# PLC-_-V1.net
KiCad netlist of a schematic drawn in Altium Designer
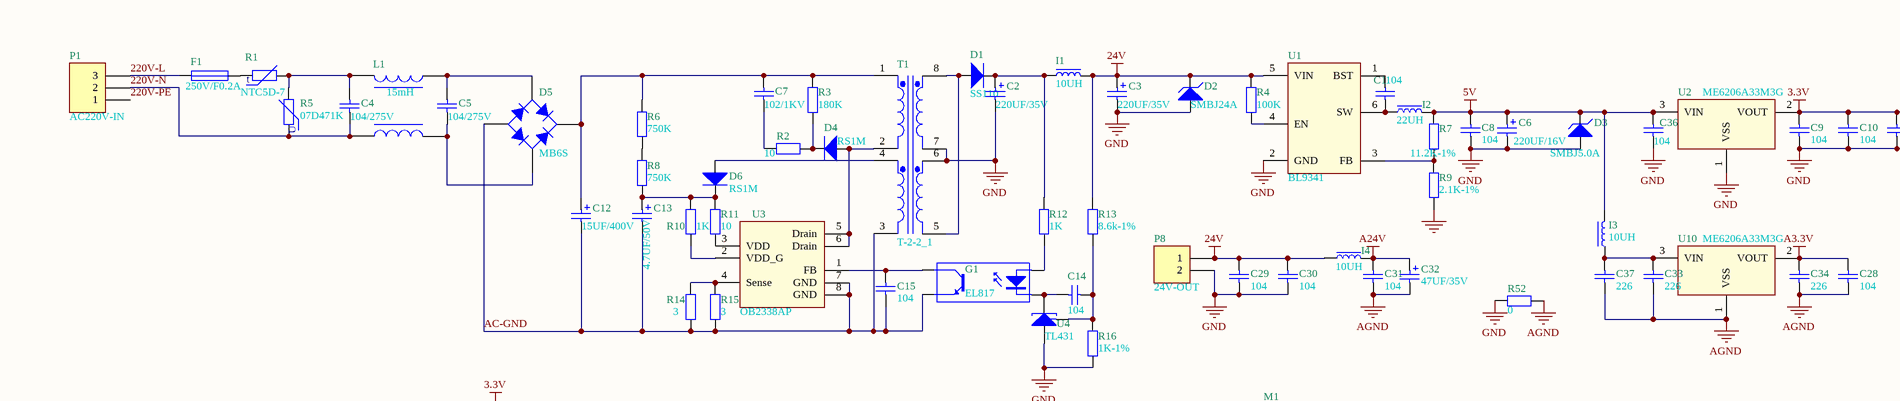
[diagram p0: PLC-无线通讯版-V1.SchDoc, top left]
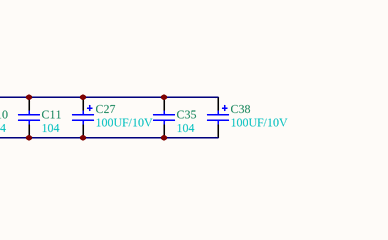
[diagram p1: PLC-无线通讯版-V1.SchDoc, top right]
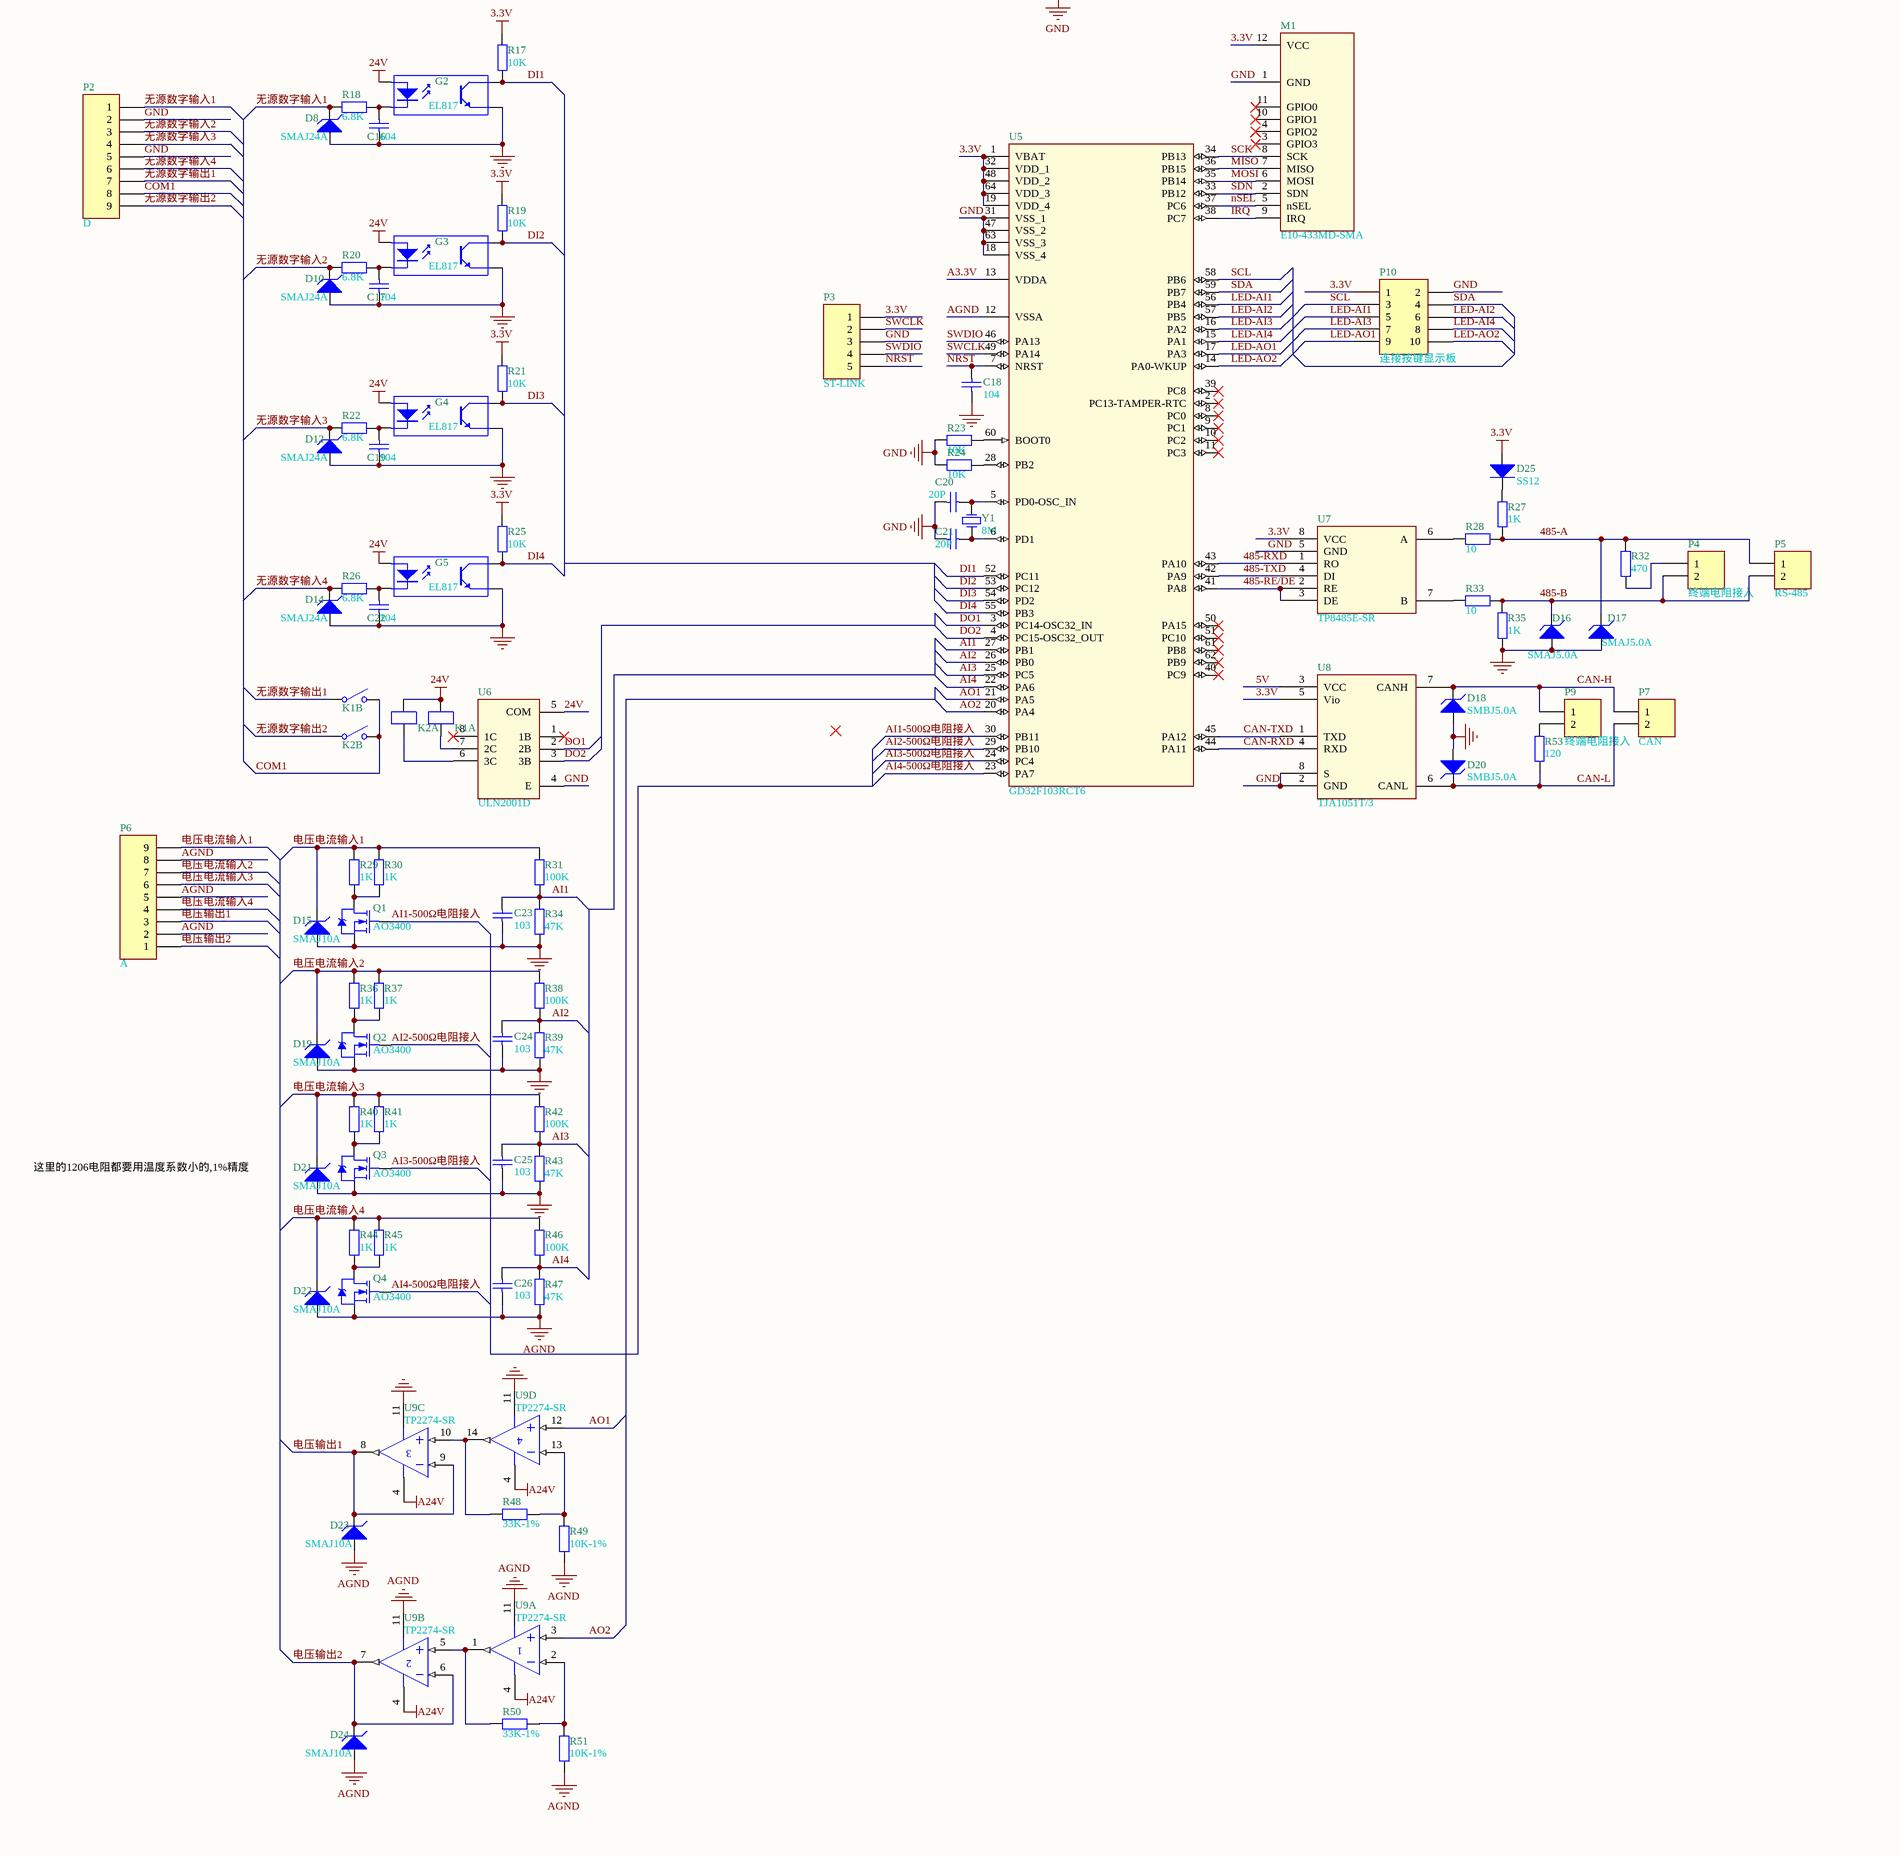
[diagram p2: PLC-无线通讯版-V1.SchDoc, bottom left]
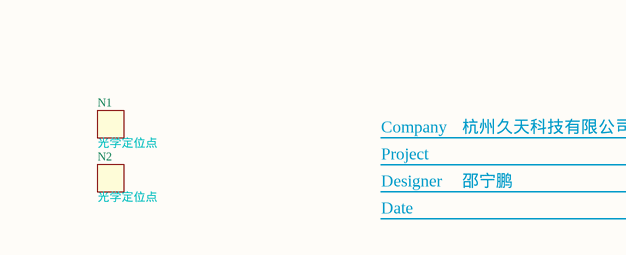
[diagram p3: PLC-无线通讯版-V1.SchDoc, bottom right]

(export (version "E")
  (design (tool "Eeschema 10.0.6"))
  (components
    (comp (ref "C1")
      (value "104")
      (footprint "C-0603")
      (description "Capacitor")
      (fields (field (name "PUBLISHER") "Altium Limited"))
      (libsource (lib "元件2.0") (part "Cap"))
    )
    (comp (ref "C2")
      (value "220UF/35V")
      (footprint "贴片固态电容8*10-M")
      (description "电解电容")
      (fields (field (name "PUBLISHER") "Altium Limited"))
      (libsource (lib "2电容-V1.0") (part "Cap Pol1"))
    )
    (comp (ref "C3")
      (value "220UF/35V")
      (footprint "贴片固态电容8*10-M")
      (description "电解电容")
      (fields (field (name "PUBLISHER") "Altium Limited"))
      (libsource (lib "2电容-V1.0") (part "Cap Pol1"))
    )
    (comp (ref "C4")
      (value "104/275V")
      (footprint "安规电容 脚距10")
      (description "Capacitor")
      (fields (field (name "PUBLISHER") "Altium Limited"))
      (libsource (lib "元件2.0") (part "Cap"))
    )
    (comp (ref "C5")
      (value "104/275V")
      (footprint "安规电容 脚距10")
      (description "Capacitor")
      (fields (field (name "PUBLISHER") "Altium Limited"))
      (libsource (lib "元件2.0") (part "Cap"))
    )
    (comp (ref "C6")
      (value "220UF/16V")
      (footprint "贴片固态电容6.3*7.7")
      (description "Polarized Capacitor (Radial)")
      (fields (field (name "PUBLISHER") "Altium Limited"))
      (libsource (lib "元件2.0") (part "Cap Pol1"))
    )
    (comp (ref "C7")
      (value "102/1KV")
      (footprint "C-1206-M")
      (description "0805")
      (fields (field (name "PUBLISHER") "Altium Limited"))
      (libsource (lib "2电容-V1.0") (part "Cap-0603"))
    )
    (comp (ref "C8")
      (value "104")
      (footprint "C-0603")
      (description "Capacitor")
      (fields (field (name "PUBLISHER") "Altium Limited"))
      (libsource (lib "元件2.0") (part "Cap"))
    )
    (comp (ref "C9")
      (value "104")
      (footprint "C-0603")
      (description "Capacitor")
      (fields (field (name "PUBLISHER") "Altium Limited"))
      (libsource (lib "元件2.0") (part "Cap"))
    )
    (comp (ref "C10")
      (value "104")
      (footprint "C-0603")
      (description "Capacitor")
      (fields (field (name "PUBLISHER") "Altium Limited"))
      (libsource (lib "元件2.0") (part "Cap"))
    )
    (comp (ref "C11")
      (value "104")
      (footprint "C-0603")
      (description "Capacitor")
      (fields (field (name "PUBLISHER") "Altium Limited"))
      (libsource (lib "元件2.0") (part "Cap"))
    )
    (comp (ref "C12")
      (value "15UF/400V")
      (footprint "电解电容10*20蓝色")
      (description "电解电容")
      (fields (field (name "PUBLISHER") "Altium Limited"))
      (libsource (lib "2电容-V1.0") (part "Cap Pol1"))
    )
    (comp (ref "C13")
      (value "4.7UF/50V")
      (footprint "贴片固态电容4*5.3")
      (description "电解电容")
      (fields (field (name "PUBLISHER") "Altium Limited"))
      (libsource (lib "2电容-V1.0") (part "Cap Pol1"))
    )
    (comp (ref "C14")
      (value "104")
      (footprint "C-0603")
      (description "Capacitor")
      (fields (field (name "PUBLISHER") "Altium Limited"))
      (libsource (lib "元件2.0") (part "Cap"))
    )
    (comp (ref "C15")
      (value "104")
      (footprint "C-0603")
      (description "Capacitor")
      (fields (field (name "PUBLISHER") "Altium Limited"))
      (libsource (lib "元件2.0") (part "Cap"))
    )
    (comp (ref "C16")
      (value "104")
      (footprint "C-0603")
      (description "0805")
      (fields (field (name "PUBLISHER") "Altium Limited"))
      (libsource (lib "2电容-V1.0") (part "Cap-0603"))
    )
    (comp (ref "C17")
      (value "104")
      (footprint "C-0603")
      (description "0805")
      (fields (field (name "PUBLISHER") "Altium Limited"))
      (libsource (lib "2电容-V1.0") (part "Cap-0603"))
    )
    (comp (ref "C18")
      (value "104")
      (footprint "C-0603")
      (description "0805")
      (fields (field (name "PUBLISHER") "Altium Limited"))
      (libsource (lib "2电容-V1.0") (part "Cap-0603"))
    )
    (comp (ref "C19")
      (value "104")
      (footprint "C-0603")
      (description "0805")
      (fields (field (name "PUBLISHER") "Altium Limited"))
      (libsource (lib "2电容-V1.0") (part "Cap-0603"))
    )
    (comp (ref "C20")
      (value "20P")
      (footprint "C-0603")
      (description "0805")
      (fields (field (name "PUBLISHER") "Altium Limited"))
      (libsource (lib "2电容-V1.0") (part "Cap-0603"))
    )
    (comp (ref "C21")
      (value "20P")
      (footprint "C-0603")
      (description "0805")
      (fields (field (name "PUBLISHER") "Altium Limited"))
      (libsource (lib "2电容-V1.0") (part "Cap-0603"))
    )
    (comp (ref "C22")
      (value "104")
      (footprint "C-0603")
      (description "0805")
      (fields (field (name "PUBLISHER") "Altium Limited"))
      (libsource (lib "2电容-V1.0") (part "Cap-0603"))
    )
    (comp (ref "C23")
      (value "103")
      (footprint "C-0603")
      (description "0805")
      (fields (field (name "PUBLISHER") "Altium Limited"))
      (libsource (lib "2电容-V1.0") (part "Cap-0603"))
    )
    (comp (ref "C24")
      (value "103")
      (footprint "C-0603")
      (description "0805")
      (fields (field (name "PUBLISHER") "Altium Limited"))
      (libsource (lib "2电容-V1.0") (part "Cap-0603"))
    )
    (comp (ref "C25")
      (value "103")
      (footprint "C-0603")
      (description "0805")
      (fields (field (name "PUBLISHER") "Altium Limited"))
      (libsource (lib "2电容-V1.0") (part "Cap-0603"))
    )
    (comp (ref "C26")
      (value "103")
      (footprint "C-0603")
      (description "0805")
      (fields (field (name "PUBLISHER") "Altium Limited"))
      (libsource (lib "2电容-V1.0") (part "Cap-0603"))
    )
    (comp (ref "C27")
      (value "100UF/10V")
      (footprint "贴片固态电容5*5.3")
      (description "Polarized Capacitor (Radial)")
      (fields (field (name "PUBLISHER") "Altium Limited"))
      (libsource (lib "元件2.0") (part "Cap Pol1"))
    )
    (comp (ref "C28")
      (value "104")
      (footprint "C-0603")
      (description "Capacitor")
      (fields (field (name "PUBLISHER") "Altium Limited"))
      (libsource (lib "元件2.0") (part "Cap"))
    )
    (comp (ref "C29")
      (value "104")
      (footprint "C-0603")
      (description "Capacitor")
      (fields (field (name "PUBLISHER") "Altium Limited"))
      (libsource (lib "元件2.0") (part "Cap"))
    )
    (comp (ref "C30")
      (value "104")
      (footprint "C-0603")
      (description "Capacitor")
      (fields (field (name "PUBLISHER") "Altium Limited"))
      (libsource (lib "元件2.0") (part "Cap"))
    )
    (comp (ref "C31")
      (value "104")
      (footprint "C-0603")
      (description "Capacitor")
      (fields (field (name "PUBLISHER") "Altium Limited"))
      (libsource (lib "元件2.0") (part "Cap"))
    )
    (comp (ref "C32")
      (value "47UF/35V")
      (footprint "贴片固态电容6.3*5.3-M")
      (description "Polarized Capacitor (Radial)")
      (fields (field (name "PUBLISHER") "Altium Limited"))
      (libsource (lib "元件2.0") (part "Cap Pol1"))
    )
    (comp (ref "C33")
      (value "226")
      (footprint "C-0805")
      (description "Capacitor")
      (fields (field (name "PUBLISHER") "Altium Limited"))
      (libsource (lib "元件2.0") (part "Cap"))
    )
    (comp (ref "C34")
      (value "226")
      (footprint "C-0805")
      (description "Capacitor")
      (fields (field (name "PUBLISHER") "Altium Limited"))
      (libsource (lib "元件2.0") (part "Cap"))
    )
    (comp (ref "C35")
      (value "104")
      (footprint "C-0603")
      (description "Capacitor")
      (fields (field (name "PUBLISHER") "Altium Limited"))
      (libsource (lib "元件2.0") (part "Cap"))
    )
    (comp (ref "C36")
      (value "104")
      (footprint "C-0603")
      (description "Capacitor")
      (fields (field (name "PUBLISHER") "Altium Limited"))
      (libsource (lib "元件2.0") (part "Cap"))
    )
    (comp (ref "C37")
      (value "226")
      (footprint "C-0805")
      (description "Capacitor")
      (fields (field (name "PUBLISHER") "Altium Limited"))
      (libsource (lib "元件2.0") (part "Cap"))
    )
    (comp (ref "C38")
      (value "100UF/10V")
      (footprint "贴片固态电容5*5.3")
      (description "Polarized Capacitor (Radial)")
      (fields (field (name "PUBLISHER") "Altium Limited"))
      (libsource (lib "元件2.0") (part "Cap Pol1"))
    )
    (comp (ref "D1")
      (value "SS110")
      (footprint "SMA")
      (description "SMA")
      (libsource (lib "4二极管-V1.1") (part "SS14"))
    )
    (comp (ref "D2")
      (value "SMBJ24A")
      (footprint "SMB-N")
      (description "SMB")
      (libsource (lib "4二极管-V1.1") (part "TVS-1"))
    )
    (comp (ref "D3")
      (value "SMBJ5.0A")
      (footprint "SMB-N")
      (description "SMB")
      (libsource (lib "4二极管-V1.1") (part "TVS-1"))
    )
    (comp (ref "D4")
      (value "RS1M")
      (footprint "SMA")
      (description "SMA")
      (libsource (lib "4二极管-V1.1") (part "SS14"))
    )
    (comp (ref "D5")
      (value "MB6S")
      (footprint "SOIC-4-MBS")
      (description "整流桥堆 MB05S-MB10S")
      (libsource (lib "4二极管-V1.1") (part "MB6S"))
    )
    (comp (ref "D6")
      (value "RS1M")
      (footprint "SMA")
      (description "SMA")
      (libsource (lib "4二极管-V1.1") (part "SS14"))
    )
    (comp (ref "D8")
      (value "SMAJ24A")
      (footprint "SMB-N")
      (description "SMB")
      (libsource (lib "4二极管-V1.1") (part "TVS-1"))
    )
    (comp (ref "D10")
      (value "SMAJ24A")
      (footprint "SMB-N")
      (description "SMB")
      (libsource (lib "4二极管-V1.1") (part "TVS-1"))
    )
    (comp (ref "D12")
      (value "SMAJ24A")
      (footprint "SMB-N")
      (description "SMB")
      (libsource (lib "4二极管-V1.1") (part "TVS-1"))
    )
    (comp (ref "D14")
      (value "SMAJ24A")
      (footprint "SMB-N")
      (description "SMB")
      (libsource (lib "4二极管-V1.1") (part "TVS-1"))
    )
    (comp (ref "D15")
      (value "SMAJ10A")
      (footprint "SMA")
      (description "SMB")
      (libsource (lib "4二极管-V1.1") (part "TVS-1"))
    )
    (comp (ref "D16")
      (value "SMAJ5.0A")
      (footprint "SMB-N")
      (description "SMB")
      (libsource (lib "4二极管-V1.1") (part "TVS-1"))
    )
    (comp (ref "D17")
      (value "SMAJ5.0A")
      (footprint "SMB-N")
      (description "SMB")
      (libsource (lib "4二极管-V1.1") (part "TVS-1"))
    )
    (comp (ref "D18")
      (value "SMBJ5.0A")
      (footprint "SMB-N")
      (description "SMB")
      (libsource (lib "4二极管-V1.1") (part "TVS-1"))
    )
    (comp (ref "D19")
      (value "SMAJ10A")
      (footprint "SMA")
      (description "SMB")
      (libsource (lib "4二极管-V1.1") (part "TVS-1"))
    )
    (comp (ref "D20")
      (value "SMBJ5.0A")
      (footprint "SMB-N")
      (description "SMB")
      (libsource (lib "4二极管-V1.1") (part "TVS-1"))
    )
    (comp (ref "D21")
      (value "SMAJ10A")
      (footprint "SMA")
      (description "SMB")
      (libsource (lib "4二极管-V1.1") (part "TVS-1"))
    )
    (comp (ref "D22")
      (value "SMAJ10A")
      (footprint "SMA")
      (description "SMB")
      (libsource (lib "4二极管-V1.1") (part "TVS-1"))
    )
    (comp (ref "D23")
      (value "SMAJ10A")
      (footprint "SMA")
      (description "SMB")
      (libsource (lib "4二极管-V1.1") (part "TVS-1"))
    )
    (comp (ref "D24")
      (value "SMAJ10A")
      (footprint "SMA")
      (description "SMB")
      (libsource (lib "4二极管-V1.1") (part "TVS-1"))
    )
    (comp (ref "D25")
      (value "SS12")
      (footprint "SMA")
      (description "SMA")
      (libsource (lib "4二极管-V1.1") (part "SS14"))
    )
    (comp (ref "F1")
      (value "250V/F0.2A")
      (footprint "FUSE-3*10带引线")
      (description "Fuse")
      (fields (field (name "PUBLISHER") "Altium Limited"))
      (libsource (lib "11其他元件-V1.0") (part "Fuse 1"))
    )
    (comp (ref "G1")
      (value "EL817")
      (footprint "SOP-4-L")
      (fields (field (name "PUBLISHER") "Altium Limited"))
      (libsource (lib "4二极管-V1.1") (part "EL817"))
    )
    (comp (ref "G2")
      (value "EL817")
      (footprint "SOP-4-L")
      (fields (field (name "PUBLISHER") "Altium Limited"))
      (libsource (lib "4二极管-V1.1") (part "EL817"))
    )
    (comp (ref "G3")
      (value "EL817")
      (footprint "SOP-4-L")
      (fields (field (name "PUBLISHER") "Altium Limited"))
      (libsource (lib "4二极管-V1.1") (part "EL817"))
    )
    (comp (ref "G4")
      (value "EL817")
      (footprint "SOP-4-L")
      (fields (field (name "PUBLISHER") "Altium Limited"))
      (libsource (lib "4二极管-V1.1") (part "EL817"))
    )
    (comp (ref "G5")
      (value "EL817")
      (footprint "SOP-4-L")
      (fields (field (name "PUBLISHER") "Altium Limited"))
      (libsource (lib "4二极管-V1.1") (part "EL817"))
    )
    (comp (ref "I1") (value "10UH") (footprint "CD43-N") (libsource (lib "3电感-V1.0") (part "Inductance3")))
    (comp (ref "I2") (value "22UH") (footprint "CD54") (libsource (lib "3电感-V1.0") (part "Inductance3")))
    (comp (ref "I3") (value "10UH") (footprint "CD43-N") (libsource (lib "3电感-V1.0") (part "Inductance3")))
    (comp (ref "I4") (value "10UH") (footprint "CD43-N") (libsource (lib "3电感-V1.0") (part "Inductance3")))
    (comp (ref "K1")
      (value "HF49FD-D24-1H11")
      (footprint "HF49FD-D24-1H11")
      (libsource (lib "") (part "HF49FD-D24-1H11_1"))
    )
    (comp (ref "K2")
      (value "HF49FD-D24-1H11")
      (footprint "HF49FD-D24-1H11")
      (libsource (lib "10继电器-V1.0") (part "HF49FD-D24-1H11"))
    )
    (comp (ref "L1") (value "15mH") (footprint "UU9.8") (libsource (lib "3电感-V1.0") (part "共模电感UU9.8")))
    (comp (ref "M1")
      (value "E10-433MD-SMA")
      (footprint "E10-433MD-SMA")
      (libsource (lib "6电路模块-V1.0") (part "E10-433MD-SMA"))
    )
    (comp (ref "N1") (value "光学定位点") (footprint "MARK-1mm-3mm") (libsource (lib "11其他元件-V1.0") (part "无引脚")))
    (comp (ref "N2") (value "光学定位点") (footprint "MARK-1mm-3mm") (libsource (lib "11其他元件-V1.0") (part "无引脚")))
    (comp (ref "P1")
      (value "AC220V-IN")
      (footprint "KF2EDGVC-5.08-3P")
      (description "Header, 3-Pin")
      (fields (field (name "PUBLISHER") "Altium Limited"))
      (libsource (lib "5排针-V1.0") (part "Header 3"))
    )
    (comp (ref "P2")
      (value "D")
      (footprint "2EMGKG-5.08-9P")
      (description "Header, 9-Pin")
      (fields (field (name "PUBLISHER") "Altium Limited"))
      (libsource (lib "5排针-V1.0") (part "Header 9"))
    )
    (comp (ref "P3")
      (value "ST-LINK")
      (footprint "5P下载口")
      (description "Header, 5-Pin")
      (fields (field (name "PUBLISHER") "Altium Limited"))
      (libsource (lib "5排针-V1.0") (part "Header 5"))
    )
    (comp (ref "P4")
      (value "终端电阻接入")
      (footprint "HDR1X2")
      (description "Header, 2-Pin")
      (fields (field (name "PUBLISHER") "Altium Limited"))
      (libsource (lib "5排针-V1.0") (part "Header 2"))
    )
    (comp (ref "P5")
      (value "RS-485")
      (footprint "2EMGKG-5.08-2P")
      (description "Header, 2-Pin")
      (fields (field (name "PUBLISHER") "Altium Limited"))
      (libsource (lib "5排针-V1.0") (part "Header 2"))
    )
    (comp (ref "P6")
      (value "A")
      (footprint "2EMGKG-5.08-9P")
      (description "Header, 9-Pin")
      (fields (field (name "PUBLISHER") "Altium Limited"))
      (libsource (lib "") (part "Header 9_1"))
    )
    (comp (ref "P7")
      (value "CAN")
      (footprint "2EMGKG-5.08-2P")
      (description "Header, 2-Pin")
      (fields (field (name "PUBLISHER") "Altium Limited"))
      (libsource (lib "5排针-V1.0") (part "Header 2"))
    )
    (comp (ref "P8")
      (value "24V-OUT")
      (footprint "2EMGKG-5.08-2P")
      (description "Header, 2-Pin")
      (fields (field (name "PUBLISHER") "Altium Limited"))
      (libsource (lib "") (part "Header 2_1"))
    )
    (comp (ref "P9")
      (value "终端电阻接入")
      (footprint "HDR1X2")
      (description "Header, 2-Pin")
      (fields (field (name "PUBLISHER") "Altium Limited"))
      (libsource (lib "5排针-V1.0") (part "Header 2"))
    )
    (comp (ref "P10")
      (value "连接按键显示板")
      (footprint "HDR2X5-贴片母座")
      (description "Header, 5-Pin, Dual row")
      (fields (field (name "PUBLISHER") "Altium Limited"))
      (libsource (lib "5排针-V1.0") (part "Header 5X2"))
    )
    (comp (ref "Q1")
      (value "AO3400")
      (footprint "SOT-23")
      (description "SOT-23")
      (libsource (lib "4二极管-V1.1") (part "AO3400"))
    )
    (comp (ref "Q2")
      (value "AO3400")
      (footprint "SOT-23")
      (description "SOT-23")
      (libsource (lib "4二极管-V1.1") (part "AO3400"))
    )
    (comp (ref "Q3")
      (value "AO3400")
      (footprint "SOT-23")
      (description "SOT-23")
      (libsource (lib "4二极管-V1.1") (part "AO3400"))
    )
    (comp (ref "Q4")
      (value "AO3400")
      (footprint "SOT-23")
      (description "SOT-23")
      (libsource (lib "4二极管-V1.1") (part "AO3400"))
    )
    (comp (ref "R1")
      (value "NTC5D-7")
      (footprint "NTC-5D-7")
      (fields (field (name "PUBLISHER") "Altium Limited"))
      (libsource (lib "1电阻-V1.0") (part "热敏电阻"))
    )
    (comp (ref "R2")
      (value "10")
      (footprint "R-0805")
      (description "0603")
      (fields (field (name "PUBLISHER") "Altium Limited"))
      (libsource (lib "") (part "Res2-0603_3"))
    )
    (comp (ref "R3")
      (value "180K")
      (footprint "R-1206-M")
      (description "0603")
      (fields (field (name "PUBLISHER") "Altium Limited"))
      (libsource (lib "1电阻-V1.0") (part "Res2-0603"))
    )
    (comp (ref "R4")
      (value "100K")
      (footprint "R-0603")
      (description "0603")
      (fields (field (name "PUBLISHER") "Altium Limited"))
      (libsource (lib "") (part "Res2-0603_1"))
    )
    (comp (ref "R5") (value "07D471K") (footprint "MOV-07D") (libsource (lib "1电阻-V1.0") (part "压敏电阻")))
    (comp (ref "R6")
      (value "750K")
      (footprint "R-1206-M")
      (description "1%")
      (fields (field (name "PUBLISHER") "Altium Limited"))
      (libsource (lib "") (part "Res2_2"))
    )
    (comp (ref "R7")
      (value "11.2K-1%")
      (footprint "R-0603")
      (description "0603")
      (fields (field (name "PUBLISHER") "Altium Limited"))
      (libsource (lib "") (part "Res2-0603_1"))
    )
    (comp (ref "R8")
      (value "750K")
      (footprint "R-1206-M")
      (description "1%")
      (fields (field (name "PUBLISHER") "Altium Limited"))
      (libsource (lib "") (part "Res2_2"))
    )
    (comp (ref "R9")
      (value "2.1K-1%")
      (footprint "R-0603")
      (description "0603")
      (fields (field (name "PUBLISHER") "Altium Limited"))
      (libsource (lib "") (part "Res2-0603_1"))
    )
    (comp (ref "R10")
      (value "1K")
      (footprint "R-0603")
      (description "0603")
      (fields (field (name "PUBLISHER") "Altium Limited"))
      (libsource (lib "1电阻-V1.0") (part "Res2-0603"))
    )
    (comp (ref "R11")
      (value "10")
      (footprint "R-0603")
      (description "0603")
      (fields (field (name "PUBLISHER") "Altium Limited"))
      (libsource (lib "1电阻-V1.0") (part "Res2-0603"))
    )
    (comp (ref "R12")
      (value "1K")
      (footprint "R-0603")
      (description "1%")
      (fields (field (name "PUBLISHER") "Altium Limited"))
      (libsource (lib "元件2.0") (part "Res2"))
    )
    (comp (ref "R13")
      (value "8.6k-1%")
      (footprint "R-0603")
      (description "1%")
      (fields (field (name "PUBLISHER") "Altium Limited"))
      (libsource (lib "元件2.0") (part "Res2"))
    )
    (comp (ref "R14")
      (value "3")
      (footprint "R-1206-M")
      (description "0603")
      (fields (field (name "PUBLISHER") "Altium Limited"))
      (libsource (lib "1电阻-V1.0") (part "Res2-0603"))
    )
    (comp (ref "R15")
      (value "3")
      (footprint "R-1206-M")
      (description "0603")
      (fields (field (name "PUBLISHER") "Altium Limited"))
      (libsource (lib "1电阻-V1.0") (part "Res2-0603"))
    )
    (comp (ref "R16")
      (value "1K-1%")
      (footprint "R-0603")
      (description "1%")
      (fields (field (name "PUBLISHER") "Altium Limited"))
      (libsource (lib "元件2.0") (part "Res2"))
    )
    (comp (ref "R17")
      (value "10K")
      (footprint "R-0603")
      (description "0603")
      (fields (field (name "PUBLISHER") "Altium Limited"))
      (libsource (lib "1电阻-V1.0") (part "Res2-0603"))
    )
    (comp (ref "R18")
      (value "6.8K")
      (footprint "R-0603")
      (description "0603")
      (fields (field (name "PUBLISHER") "Altium Limited"))
      (libsource (lib "") (part "Res2-0603_3"))
    )
    (comp (ref "R19")
      (value "10K")
      (footprint "R-0603")
      (description "0603")
      (fields (field (name "PUBLISHER") "Altium Limited"))
      (libsource (lib "1电阻-V1.0") (part "Res2-0603"))
    )
    (comp (ref "R20")
      (value "6.8K")
      (footprint "R-0603")
      (description "0603")
      (fields (field (name "PUBLISHER") "Altium Limited"))
      (libsource (lib "") (part "Res2-0603_3"))
    )
    (comp (ref "R21")
      (value "10K")
      (footprint "R-0603")
      (description "0603")
      (fields (field (name "PUBLISHER") "Altium Limited"))
      (libsource (lib "1电阻-V1.0") (part "Res2-0603"))
    )
    (comp (ref "R22")
      (value "6.8K")
      (footprint "R-0603")
      (description "0603")
      (fields (field (name "PUBLISHER") "Altium Limited"))
      (libsource (lib "") (part "Res2-0603_3"))
    )
    (comp (ref "R23")
      (value "10K")
      (footprint "R-0603")
      (description "0603")
      (fields (field (name "PUBLISHER") "Altium Limited"))
      (libsource (lib "") (part "Res2-0603_1"))
    )
    (comp (ref "R24")
      (value "10K")
      (footprint "R-0603")
      (description "0603")
      (fields (field (name "PUBLISHER") "Altium Limited"))
      (libsource (lib "") (part "Res2-0603_1"))
    )
    (comp (ref "R25")
      (value "10K")
      (footprint "R-0603")
      (description "0603")
      (fields (field (name "PUBLISHER") "Altium Limited"))
      (libsource (lib "1电阻-V1.0") (part "Res2-0603"))
    )
    (comp (ref "R26")
      (value "6.8K")
      (footprint "R-0603")
      (description "0603")
      (fields (field (name "PUBLISHER") "Altium Limited"))
      (libsource (lib "") (part "Res2-0603_3"))
    )
    (comp (ref "R27")
      (value "1K")
      (footprint "R-0603")
      (description "Resistor")
      (fields (field (name "PUBLISHER") "Altium Limited"))
      (libsource (lib "") (part "Res2_3"))
    )
    (comp (ref "R28")
      (value "10")
      (footprint "R-0805-M")
      (description "Resistor")
      (fields (field (name "PUBLISHER") "Altium Limited"))
      (libsource (lib "") (part "Res2_1"))
    )
    (comp (ref "R29")
      (value "1K")
      (footprint "R-1206-M")
      (description "0603")
      (fields (field (name "PUBLISHER") "Altium Limited"))
      (libsource (lib "1电阻-V1.0") (part "Res2-0603"))
    )
    (comp (ref "R30")
      (value "1K")
      (footprint "R-1206-M")
      (description "0603")
      (fields (field (name "PUBLISHER") "Altium Limited"))
      (libsource (lib "1电阻-V1.0") (part "Res2-0603"))
    )
    (comp (ref "R31")
      (value "100K")
      (footprint "R-1206-M")
      (description "0603")
      (fields (field (name "PUBLISHER") "Altium Limited"))
      (libsource (lib "1电阻-V1.0") (part "Res2-0603"))
    )
    (comp (ref "R32")
      (value "470")
      (footprint "R-1206-M")
      (description "Resistor")
      (fields (field (name "PUBLISHER") "Altium Limited"))
      (libsource (lib "Miscellaneous Devices") (part "Res2"))
    )
    (comp (ref "R33")
      (value "10")
      (footprint "R-0805-M")
      (description "Resistor")
      (fields (field (name "PUBLISHER") "Altium Limited"))
      (libsource (lib "") (part "Res2_1"))
    )
    (comp (ref "R34")
      (value "47K")
      (footprint "R-1206-M")
      (description "0603")
      (fields (field (name "PUBLISHER") "Altium Limited"))
      (libsource (lib "1电阻-V1.0") (part "Res2-0603"))
    )
    (comp (ref "R35")
      (value "1K")
      (footprint "R-0603")
      (description "Resistor")
      (fields (field (name "PUBLISHER") "Altium Limited"))
      (libsource (lib "") (part "Res2_1"))
    )
    (comp (ref "R36")
      (value "1K")
      (footprint "R-1206-M")
      (description "0603")
      (fields (field (name "PUBLISHER") "Altium Limited"))
      (libsource (lib "1电阻-V1.0") (part "Res2-0603"))
    )
    (comp (ref "R37")
      (value "1K")
      (footprint "R-1206-M")
      (description "0603")
      (fields (field (name "PUBLISHER") "Altium Limited"))
      (libsource (lib "1电阻-V1.0") (part "Res2-0603"))
    )
    (comp (ref "R38")
      (value "100K")
      (footprint "R-1206-M")
      (description "0603")
      (fields (field (name "PUBLISHER") "Altium Limited"))
      (libsource (lib "1电阻-V1.0") (part "Res2-0603"))
    )
    (comp (ref "R39")
      (value "47K")
      (footprint "R-1206-M")
      (description "0603")
      (fields (field (name "PUBLISHER") "Altium Limited"))
      (libsource (lib "1电阻-V1.0") (part "Res2-0603"))
    )
    (comp (ref "R40")
      (value "1K")
      (footprint "R-1206-M")
      (description "0603")
      (fields (field (name "PUBLISHER") "Altium Limited"))
      (libsource (lib "1电阻-V1.0") (part "Res2-0603"))
    )
    (comp (ref "R41")
      (value "1K")
      (footprint "R-1206-M")
      (description "0603")
      (fields (field (name "PUBLISHER") "Altium Limited"))
      (libsource (lib "1电阻-V1.0") (part "Res2-0603"))
    )
    (comp (ref "R42")
      (value "100K")
      (footprint "R-1206-M")
      (description "0603")
      (fields (field (name "PUBLISHER") "Altium Limited"))
      (libsource (lib "1电阻-V1.0") (part "Res2-0603"))
    )
    (comp (ref "R43")
      (value "47K")
      (footprint "R-1206-M")
      (description "0603")
      (fields (field (name "PUBLISHER") "Altium Limited"))
      (libsource (lib "1电阻-V1.0") (part "Res2-0603"))
    )
    (comp (ref "R44")
      (value "1K")
      (footprint "R-1206-M")
      (description "0603")
      (fields (field (name "PUBLISHER") "Altium Limited"))
      (libsource (lib "1电阻-V1.0") (part "Res2-0603"))
    )
    (comp (ref "R45")
      (value "1K")
      (footprint "R-1206-M")
      (description "0603")
      (fields (field (name "PUBLISHER") "Altium Limited"))
      (libsource (lib "1电阻-V1.0") (part "Res2-0603"))
    )
    (comp (ref "R46")
      (value "100K")
      (footprint "R-1206-M")
      (description "0603")
      (fields (field (name "PUBLISHER") "Altium Limited"))
      (libsource (lib "1电阻-V1.0") (part "Res2-0603"))
    )
    (comp (ref "R47")
      (value "47K")
      (footprint "R-1206-M")
      (description "0603")
      (fields (field (name "PUBLISHER") "Altium Limited"))
      (libsource (lib "1电阻-V1.0") (part "Res2-0603"))
    )
    (comp (ref "R48")
      (value "33K-1%")
      (footprint "R-0603")
      (description "0603")
      (fields (field (name "PUBLISHER") "Altium Limited"))
      (libsource (lib "") (part "Res2-0603_1"))
    )
    (comp (ref "R49")
      (value "10K-1%")
      (footprint "R-0603")
      (description "0603")
      (fields (field (name "PUBLISHER") "Altium Limited"))
      (libsource (lib "") (part "Res2-0603_2"))
    )
    (comp (ref "R50")
      (value "33K-1%")
      (footprint "R-0603")
      (description "0603")
      (fields (field (name "PUBLISHER") "Altium Limited"))
      (libsource (lib "") (part "Res2-0603_1"))
    )
    (comp (ref "R51")
      (value "10K-1%")
      (footprint "R-0603")
      (description "0603")
      (fields (field (name "PUBLISHER") "Altium Limited"))
      (libsource (lib "") (part "Res2-0603_2"))
    )
    (comp (ref "R52")
      (value "0")
      (footprint "R-0603")
      (description "0603")
      (fields (field (name "PUBLISHER") "Altium Limited"))
      (libsource (lib "1电阻-V1.0") (part "Res2-0603"))
    )
    (comp (ref "R53")
      (value "120")
      (footprint "R-1206")
      (description "Resistor")
      (fields (field (name "PUBLISHER") "Altium Limited"))
      (libsource (lib "Miscellaneous Devices") (part "Res2"))
    )
    (comp (ref "T1") (value "T-2-2_1") (footprint "EE19-卧式") (libsource (lib "3电感-V1.0") (part "T-2-2_1")))
    (comp (ref "U1") (value "BL9341") (footprint "SOT-23-6-N") (libsource (lib "电源芯片DC-DC") (part "BL9341")))
    (comp (ref "U2")
      (value "ME6206A33M3G")
      (footprint "SOT-23")
      (description "LDO稳压 SOT-23")
      (libsource (lib "电源芯片-线性稳压-V1") (part "ME6206A33M3G"))
    )
    (comp (ref "U3") (value "OB2338AP") (footprint "DIP8") (libsource (lib "AC-DC控制芯片") (part "OB2338AP")))
    (comp (ref "U4")
      (value "TL431")
      (footprint "SOT-23")
      (description "稳压芯片 SOT-23")
      (libsource (lib "电源芯片-线性稳压-V1") (part "TL431"))
    )
    (comp (ref "U5")
      (value "GD32F103RCT6")
      (footprint "LQFP64-M")
      (libsource (lib "9单片机-V1.0") (part "STM32F103RBT6"))
    )
    (comp (ref "U6")
      (value "ULN2001D")
      (footprint "SOP-8-M")
      (libsource (lib "8集成电路-V1.1") (part "ULN2001D"))
    )
    (comp (ref "U7")
      (value "TP8485E-SR")
      (footprint "SOP-8-N")
      (description "RS485总线转串口")
      (libsource (lib "集成电路1.0") (part "MAX3082"))
    )
    (comp (ref "U8") (value "TJA1051T/3") (footprint "SOP-8-N") (libsource (lib "通讯-V1") (part "TJA1051T/3")))
    (comp (ref "U9")
      (value "TP2274-SR")
      (footprint "SOP-14-M")
      (description "四运放-SOP-14")
      (libsource (lib "8集成电路-V1.1") (part "MCP6004"))
    )
    (comp (ref "U10")
      (value "ME6206A33M3G")
      (footprint "SOT-23")
      (description "LDO稳压 SOT-23")
      (libsource (lib "电源芯片-线性稳压-V1") (part "ME6206A33M3G"))
    )
    (comp (ref "Y1") (value "8M") (footprint "HC-49SMD") (libsource (lib "11其他元件-V1.0") (part "晶振")))
  )
  (nets
    (net (code "1") (name "/220V-L") (class "Default")
      (node (ref "F1") (pin "1") (pinfunction "1_1") (pintype "passive"))
      (node (ref "P1") (pin "3") (pinfunction "3_3") (pintype "passive"))
    )
    (net (code "2") (name "/220V-N") (class "Default")
      (node (ref "C4") (pin "2") (pinfunction "2_2") (pintype "passive"))
      (node (ref "L1") (pin "1") (pinfunction "1_1") (pintype "passive"))
      (node (ref "P1") (pin "2") (pinfunction "2_2") (pintype "passive"))
      (node (ref "R5") (pin "1") (pinfunction "1_1") (pintype "passive"))
    )
    (net (code "3") (name "/220V-PE") (class "Default")
      (node (ref "P1") (pin "1") (pinfunction "1_1") (pintype "passive"))
    )
    (net (code "4") (name "/485-A") (class "Default")
      (node (ref "D17") (pin "2") (pinfunction "K_2") (pintype "passive"))
      (node (ref "P5") (pin "1") (pinfunction "1_1") (pintype "passive"))
      (node (ref "R27") (pin "2") (pinfunction "2_2") (pintype "passive"))
      (node (ref "R28") (pin "1") (pinfunction "1_1") (pintype "passive"))
      (node (ref "R32") (pin "1") (pinfunction "1_1") (pintype "passive"))
    )
    (net (code "5") (name "/485-B") (class "Default")
      (node (ref "D16") (pin "2") (pinfunction "K_2") (pintype "passive"))
      (node (ref "P4") (pin "2") (pinfunction "2_2") (pintype "passive"))
      (node (ref "P5") (pin "2") (pinfunction "2_2") (pintype "passive"))
      (node (ref "R33") (pin "1") (pinfunction "1_1") (pintype "passive"))
      (node (ref "R35") (pin "2") (pinfunction "2_2") (pintype "passive"))
    )
    (net (code "6") (name "/485-RE{slash}DE") (class "Default")
      (node (ref "U5") (pin "41") (pinfunction "PA8_41") (pintype "bidirectional"))
      (node (ref "U7") (pin "2") (pinfunction "RE_2") (pintype "passive"))
      (node (ref "U7") (pin "3") (pinfunction "DE_3") (pintype "passive"))
    )
    (net (code "7") (name "/485-RXD") (class "Default")
      (node (ref "U5") (pin "43") (pinfunction "PA10_43") (pintype "bidirectional"))
      (node (ref "U7") (pin "1") (pinfunction "RO_1") (pintype "passive"))
    )
    (net (code "8") (name "/485-TXD") (class "Default")
      (node (ref "U5") (pin "42") (pinfunction "PA9_42") (pintype "bidirectional"))
      (node (ref "U7") (pin "4") (pinfunction "DI_4") (pintype "passive"))
    )
    (net (code "9") (name "/AC-GND") (class "Default")
      (node (ref "C12") (pin "2") (pinfunction "2_2") (pintype "passive"))
      (node (ref "C13") (pin "2") (pinfunction "2_2") (pintype "passive"))
      (node (ref "C15") (pin "1") (pinfunction "1_1") (pintype "passive"))
      (node (ref "D5") (pin "4") (pinfunction "A_4") (pintype "passive"))
      (node (ref "G1") (pin "3") (pinfunction "E_3") (pintype "passive"))
      (node (ref "R14") (pin "1") (pinfunction "1_1") (pintype "passive"))
      (node (ref "R15") (pin "1") (pinfunction "1_1") (pintype "passive"))
      (node (ref "T1") (pin "3") (pinfunction "3_3") (pintype "passive"))
      (node (ref "U3") (pin "7") (pinfunction "GND_7") (pintype "passive"))
      (node (ref "U3") (pin "8") (pinfunction "GND_8") (pintype "passive"))
    )
    (net (code "10") (name "/AI1") (class "Default")
      (node (ref "C23") (pin "2") (pinfunction "2_2") (pintype "passive"))
      (node (ref "R31") (pin "1") (pinfunction "1_1") (pintype "passive"))
      (node (ref "R34") (pin "2") (pinfunction "2_2") (pintype "passive"))
      (node (ref "U5") (pin "27") (pinfunction "PB1_27") (pintype "bidirectional"))
    )
    (net (code "11") (name "/AI1-500Ω电阻接入") (class "Default")
      (node (ref "Q1") (pin "1") (pinfunction "G_1") (pintype "passive"))
      (node (ref "U5") (pin "30") (pinfunction "PB11_30") (pintype "bidirectional"))
    )
    (net (code "12") (name "/AI2") (class "Default")
      (node (ref "C24") (pin "2") (pinfunction "2_2") (pintype "passive"))
      (node (ref "R38") (pin "1") (pinfunction "1_1") (pintype "passive"))
      (node (ref "R39") (pin "2") (pinfunction "2_2") (pintype "passive"))
      (node (ref "U5") (pin "26") (pinfunction "PB0_26") (pintype "bidirectional"))
    )
    (net (code "13") (name "/AI2-500Ω电阻接入") (class "Default")
      (node (ref "Q2") (pin "1") (pinfunction "G_1") (pintype "passive"))
      (node (ref "U5") (pin "29") (pinfunction "PB10_29") (pintype "bidirectional"))
    )
    (net (code "14") (name "/AI3") (class "Default")
      (node (ref "C25") (pin "2") (pinfunction "2_2") (pintype "passive"))
      (node (ref "R42") (pin "1") (pinfunction "1_1") (pintype "passive"))
      (node (ref "R43") (pin "2") (pinfunction "2_2") (pintype "passive"))
      (node (ref "U5") (pin "25") (pinfunction "PC5_25") (pintype "bidirectional"))
    )
    (net (code "15") (name "/AI3-500Ω电阻接入") (class "Default")
      (node (ref "Q3") (pin "1") (pinfunction "G_1") (pintype "passive"))
      (node (ref "U5") (pin "24") (pinfunction "PC4_24") (pintype "bidirectional"))
    )
    (net (code "16") (name "/AI4") (class "Default")
      (node (ref "C26") (pin "2") (pinfunction "2_2") (pintype "passive"))
      (node (ref "R46") (pin "1") (pinfunction "1_1") (pintype "passive"))
      (node (ref "R47") (pin "2") (pinfunction "2_2") (pintype "passive"))
      (node (ref "U5") (pin "22") (pinfunction "PA6_22") (pintype "bidirectional"))
    )
    (net (code "17") (name "/AI4-500Ω电阻接入") (class "Default")
      (node (ref "Q4") (pin "1") (pinfunction "G_1") (pintype "passive"))
      (node (ref "U5") (pin "23") (pinfunction "PA7_23") (pintype "bidirectional"))
    )
    (net (code "18") (name "/AO1") (class "Default")
      (node (ref "U5") (pin "21") (pinfunction "PA5_21") (pintype "bidirectional"))
      (node (ref "U9") (pin "12") (pinfunction "IN+_12") (pintype "input"))
    )
    (net (code "19") (name "/AO2") (class "Default")
      (node (ref "U5") (pin "20") (pinfunction "PA4_20") (pintype "bidirectional"))
      (node (ref "U9") (pin "3") (pinfunction "IN+_3") (pintype "input"))
    )
    (net (code "20") (name "/CAN-H") (class "Default")
      (node (ref "D18") (pin "2") (pinfunction "K_2") (pintype "passive"))
      (node (ref "P7") (pin "1") (pinfunction "1_1") (pintype "passive"))
      (node (ref "P9") (pin "1") (pinfunction "1_1") (pintype "passive"))
      (node (ref "U8") (pin "7") (pinfunction "CANH_7") (pintype "passive"))
    )
    (net (code "21") (name "/CAN-L") (class "Default")
      (node (ref "D20") (pin "2") (pinfunction "K_2") (pintype "passive"))
      (node (ref "P7") (pin "2") (pinfunction "2_2") (pintype "passive"))
      (node (ref "R53") (pin "2") (pinfunction "2_2") (pintype "passive"))
      (node (ref "U8") (pin "6") (pinfunction "CANL_6") (pintype "passive"))
    )
    (net (code "22") (name "/CAN-RXD") (class "Default")
      (node (ref "U5") (pin "44") (pinfunction "PA11_44") (pintype "bidirectional"))
      (node (ref "U8") (pin "4") (pinfunction "RXD_4") (pintype "passive"))
    )
    (net (code "23") (name "/CAN-TXD") (class "Default")
      (node (ref "U5") (pin "45") (pinfunction "PA12_45") (pintype "bidirectional"))
      (node (ref "U8") (pin "1") (pinfunction "TXD_1") (pintype "passive"))
    )
    (net (code "24") (name "/COM1") (class "Default")
      (node (ref "K1") (pin "4") (pinfunction "4_4") (pintype "passive"))
      (node (ref "K2") (pin "4") (pinfunction "4_4") (pintype "passive"))
      (node (ref "P2") (pin "8") (pinfunction "8_8") (pintype "passive"))
    )
    (net (code "25") (name "/DI1") (class "Default")
      (node (ref "G2") (pin "4") (pinfunction "C_4") (pintype "passive"))
      (node (ref "R17") (pin "1") (pinfunction "1_1") (pintype "passive"))
      (node (ref "U5") (pin "52") (pinfunction "PC11_52") (pintype "bidirectional"))
    )
    (net (code "26") (name "/DI2") (class "Default")
      (node (ref "G3") (pin "4") (pinfunction "C_4") (pintype "passive"))
      (node (ref "R19") (pin "1") (pinfunction "1_1") (pintype "passive"))
      (node (ref "U5") (pin "53") (pinfunction "PC12_53") (pintype "bidirectional"))
    )
    (net (code "27") (name "/DI3") (class "Default")
      (node (ref "G4") (pin "4") (pinfunction "C_4") (pintype "passive"))
      (node (ref "R21") (pin "1") (pinfunction "1_1") (pintype "passive"))
      (node (ref "U5") (pin "54") (pinfunction "PD2_54") (pintype "bidirectional"))
    )
    (net (code "28") (name "/DI4") (class "Default")
      (node (ref "G5") (pin "4") (pinfunction "C_4") (pintype "passive"))
      (node (ref "R25") (pin "1") (pinfunction "1_1") (pintype "passive"))
      (node (ref "U5") (pin "55") (pinfunction "PB3_55") (pintype "bidirectional"))
    )
    (net (code "29") (name "/DO1") (class "Default")
      (node (ref "U5") (pin "3") (pinfunction "PC14-OSC32_IN_3") (pintype "bidirectional"))
      (node (ref "U6") (pin "2") (pinfunction "2B_2") (pintype "passive"))
    )
    (net (code "30") (name "/DO2") (class "Default")
      (node (ref "U5") (pin "4") (pinfunction "PC15-OSC32_OUT_4") (pintype "bidirectional"))
      (node (ref "U6") (pin "3") (pinfunction "3B_3") (pintype "passive"))
    )
    (net (code "31") (name "/IRQ") (class "Default")
      (node (ref "M1") (pin "9") (pinfunction "IRQ_9") (pintype "passive"))
      (node (ref "U5") (pin "38") (pinfunction "PC7_38") (pintype "bidirectional"))
    )
    (net (code "32") (name "/LED-AI1") (class "Default")
      (node (ref "P10") (pin "5") (pinfunction "5_5") (pintype "passive"))
      (node (ref "U5") (pin "56") (pinfunction "PB4_56") (pintype "bidirectional"))
    )
    (net (code "33") (name "/LED-AI2") (class "Default")
      (node (ref "P10") (pin "6") (pinfunction "6_6") (pintype "passive"))
      (node (ref "U5") (pin "57") (pinfunction "PB5_57") (pintype "bidirectional"))
    )
    (net (code "34") (name "/LED-AI3") (class "Default")
      (node (ref "P10") (pin "7") (pinfunction "7_7") (pintype "passive"))
      (node (ref "U5") (pin "16") (pinfunction "PA2_16") (pintype "bidirectional"))
    )
    (net (code "35") (name "/LED-AI4") (class "Default")
      (node (ref "P10") (pin "8") (pinfunction "8_8") (pintype "passive"))
      (node (ref "U5") (pin "15") (pinfunction "PA1_15") (pintype "bidirectional"))
    )
    (net (code "36") (name "/LED-AO1") (class "Default")
      (node (ref "P10") (pin "9") (pinfunction "9_9") (pintype "passive"))
      (node (ref "U5") (pin "17") (pinfunction "PA3_17") (pintype "bidirectional"))
    )
    (net (code "37") (name "/LED-AO2") (class "Default")
      (node (ref "P10") (pin "10") (pinfunction "10_10") (pintype "passive"))
      (node (ref "U5") (pin "14") (pinfunction "PA0-WKUP_14") (pintype "bidirectional"))
    )
    (net (code "38") (name "/MISO") (class "Default")
      (node (ref "M1") (pin "7") (pinfunction "MISO_7") (pintype "passive"))
      (node (ref "U5") (pin "36") (pinfunction "PB15_36") (pintype "bidirectional"))
    )
    (net (code "39") (name "/MOSI") (class "Default")
      (node (ref "M1") (pin "6") (pinfunction "MOSI_6") (pintype "passive"))
      (node (ref "U5") (pin "35") (pinfunction "PB14_35") (pintype "bidirectional"))
    )
    (net (code "40") (name "/NRST") (class "Default")
      (node (ref "C18") (pin "2") (pinfunction "2_2") (pintype "passive"))
      (node (ref "P3") (pin "5") (pinfunction "5_5") (pintype "passive"))
      (node (ref "U5") (pin "7") (pinfunction "NRST_7") (pintype "bidirectional"))
    )
    (net (code "41") (name "/SCK") (class "Default")
      (node (ref "M1") (pin "8") (pinfunction "SCK_8") (pintype "passive"))
      (node (ref "U5") (pin "34") (pinfunction "PB13_34") (pintype "bidirectional"))
    )
    (net (code "42") (name "/SCL") (class "Default")
      (node (ref "P10") (pin "3") (pinfunction "3_3") (pintype "passive"))
      (node (ref "U5") (pin "58") (pinfunction "PB6_58") (pintype "bidirectional"))
    )
    (net (code "43") (name "/SDA") (class "Default")
      (node (ref "P10") (pin "4") (pinfunction "4_4") (pintype "passive"))
      (node (ref "U5") (pin "59") (pinfunction "PB7_59") (pintype "bidirectional"))
    )
    (net (code "44") (name "/SDN") (class "Default")
      (node (ref "M1") (pin "2") (pinfunction "SDN_2") (pintype "passive"))
      (node (ref "U5") (pin "33") (pinfunction "PB12_33") (pintype "bidirectional"))
    )
    (net (code "45") (name "/SWCLK") (class "Default")
      (node (ref "P3") (pin "2") (pinfunction "2_2") (pintype "passive"))
      (node (ref "U5") (pin "49") (pinfunction "PA14_49") (pintype "bidirectional"))
    )
    (net (code "46") (name "/SWDIO") (class "Default")
      (node (ref "P3") (pin "4") (pinfunction "4_4") (pintype "passive"))
      (node (ref "U5") (pin "46") (pinfunction "PA13_46") (pintype "bidirectional"))
    )
    (net (code "47") (name "/nSEL") (class "Default")
      (node (ref "M1") (pin "5") (pinfunction "nSEL_5") (pintype "passive"))
      (node (ref "U5") (pin "37") (pinfunction "PC6_37") (pintype "bidirectional"))
    )
    (net (code "48") (name "/无源数字输入1") (class "Default")
      (node (ref "D8") (pin "2") (pinfunction "K_2") (pintype "passive"))
      (node (ref "P2") (pin "1") (pinfunction "1_1") (pintype "passive"))
      (node (ref "R18") (pin "1") (pinfunction "1_1") (pintype "passive"))
    )
    (net (code "49") (name "/无源数字输入2") (class "Default")
      (node (ref "D10") (pin "2") (pinfunction "K_2") (pintype "passive"))
      (node (ref "P2") (pin "3") (pinfunction "3_3") (pintype "passive"))
      (node (ref "R20") (pin "1") (pinfunction "1_1") (pintype "passive"))
    )
    (net (code "50") (name "/无源数字输入3") (class "Default")
      (node (ref "D12") (pin "2") (pinfunction "K_2") (pintype "passive"))
      (node (ref "P2") (pin "4") (pinfunction "4_4") (pintype "passive"))
      (node (ref "R22") (pin "1") (pinfunction "1_1") (pintype "passive"))
    )
    (net (code "51") (name "/无源数字输入4") (class "Default")
      (node (ref "D14") (pin "2") (pinfunction "K_2") (pintype "passive"))
      (node (ref "P2") (pin "6") (pinfunction "6_6") (pintype "passive"))
      (node (ref "R26") (pin "1") (pinfunction "1_1") (pintype "passive"))
    )
    (net (code "52") (name "/无源数字输出1") (class "Default")
      (node (ref "K1") (pin "3") (pinfunction "3_3") (pintype "passive"))
      (node (ref "P2") (pin "7") (pinfunction "7_7") (pintype "passive"))
    )
    (net (code "53") (name "/无源数字输出2") (class "Default")
      (node (ref "K2") (pin "3") (pinfunction "3_3") (pintype "passive"))
      (node (ref "P2") (pin "9") (pinfunction "9_9") (pintype "passive"))
    )
    (net (code "54") (name "/电压电流输入1") (class "Default")
      (node (ref "D15") (pin "2") (pinfunction "K_2") (pintype "passive"))
      (node (ref "P6") (pin "9") (pinfunction "9_9") (pintype "passive"))
      (node (ref "R29") (pin "2") (pinfunction "2_2") (pintype "passive"))
      (node (ref "R30") (pin "2") (pinfunction "2_2") (pintype "passive"))
      (node (ref "R31") (pin "2") (pinfunction "2_2") (pintype "passive"))
    )
    (net (code "55") (name "/电压电流输入2") (class "Default")
      (node (ref "D19") (pin "2") (pinfunction "K_2") (pintype "passive"))
      (node (ref "P6") (pin "7") (pinfunction "7_7") (pintype "passive"))
      (node (ref "R36") (pin "2") (pinfunction "2_2") (pintype "passive"))
      (node (ref "R37") (pin "2") (pinfunction "2_2") (pintype "passive"))
      (node (ref "R38") (pin "2") (pinfunction "2_2") (pintype "passive"))
    )
    (net (code "56") (name "/电压电流输入3") (class "Default")
      (node (ref "D21") (pin "2") (pinfunction "K_2") (pintype "passive"))
      (node (ref "P6") (pin "6") (pinfunction "6_6") (pintype "passive"))
      (node (ref "R40") (pin "2") (pinfunction "2_2") (pintype "passive"))
      (node (ref "R41") (pin "2") (pinfunction "2_2") (pintype "passive"))
      (node (ref "R42") (pin "2") (pinfunction "2_2") (pintype "passive"))
    )
    (net (code "57") (name "/电压电流输入4") (class "Default")
      (node (ref "D22") (pin "2") (pinfunction "K_2") (pintype "passive"))
      (node (ref "P6") (pin "4") (pinfunction "4_4") (pintype "passive"))
      (node (ref "R44") (pin "2") (pinfunction "2_2") (pintype "passive"))
      (node (ref "R45") (pin "2") (pinfunction "2_2") (pintype "passive"))
      (node (ref "R46") (pin "2") (pinfunction "2_2") (pintype "passive"))
    )
    (net (code "58") (name "/电压输出1") (class "Default")
      (node (ref "D23") (pin "2") (pinfunction "K_2") (pintype "passive"))
      (node (ref "P6") (pin "3") (pinfunction "3_3") (pintype "passive"))
      (node (ref "U9") (pin "8") (pinfunction "OUT_8") (pintype "output"))
      (node (ref "U9") (pin "9") (pinfunction "IN-_9") (pintype "input"))
    )
    (net (code "59") (name "/电压输出2") (class "Default")
      (node (ref "D24") (pin "2") (pinfunction "K_2") (pintype "passive"))
      (node (ref "P6") (pin "1") (pinfunction "1_1") (pintype "passive"))
      (node (ref "U9") (pin "6") (pinfunction "IN-_6") (pintype "input"))
      (node (ref "U9") (pin "7") (pinfunction "OUT_7") (pintype "output"))
    )
    (net (code "60") (name "3.3V") (class "Default")
      (node (ref "C10") (pin "2") (pinfunction "2_2") (pintype "passive"))
      (node (ref "C11") (pin "2") (pinfunction "2_2") (pintype "passive"))
      (node (ref "C27") (pin "1") (pinfunction "1_1") (pintype "passive"))
      (node (ref "C35") (pin "2") (pinfunction "2_2") (pintype "passive"))
      (node (ref "C38") (pin "1") (pinfunction "1_1") (pintype "passive"))
      (node (ref "C9") (pin "2") (pinfunction "2_2") (pintype "passive"))
      (node (ref "D25") (pin "1") (pinfunction "A_1") (pintype "passive"))
      (node (ref "M1") (pin "12") (pinfunction "VCC_12") (pintype "passive"))
      (node (ref "P10") (pin "1") (pinfunction "1_1") (pintype "passive"))
      (node (ref "P3") (pin "1") (pinfunction "1_1") (pintype "passive"))
      (node (ref "R17") (pin "2") (pinfunction "2_2") (pintype "passive"))
      (node (ref "R19") (pin "2") (pinfunction "2_2") (pintype "passive"))
      (node (ref "R21") (pin "2") (pinfunction "2_2") (pintype "passive"))
      (node (ref "R25") (pin "2") (pinfunction "2_2") (pintype "passive"))
      (node (ref "U2") (pin "2") (pinfunction "VOUT_2") (pintype "passive"))
      (node (ref "U5") (pin "1") (pinfunction "VBAT_1") (pintype "power_in"))
      (node (ref "U5") (pin "19") (pinfunction "VDD_4_19") (pintype "power_in"))
      (node (ref "U5") (pin "32") (pinfunction "VDD_1_32") (pintype "power_in"))
      (node (ref "U5") (pin "48") (pinfunction "VDD_2_48") (pintype "power_in"))
      (node (ref "U5") (pin "64") (pinfunction "VDD_3_64") (pintype "power_in"))
      (node (ref "U7") (pin "8") (pinfunction "VCC_8") (pintype "passive"))
      (node (ref "U8") (pin "5") (pinfunction "Vio_5") (pintype "passive"))
    )
    (net (code "61") (name "5V") (class "Default")
      (node (ref "C36") (pin "2") (pinfunction "2_2") (pintype "passive"))
      (node (ref "C6") (pin "1") (pinfunction "1_1") (pintype "passive"))
      (node (ref "C8") (pin "2") (pinfunction "2_2") (pintype "passive"))
      (node (ref "D3") (pin "2") (pinfunction "K_2") (pintype "passive"))
      (node (ref "I2") (pin "2") (pinfunction "2_2") (pintype "passive"))
      (node (ref "I3") (pin "2") (pinfunction "2_2") (pintype "passive"))
      (node (ref "R7") (pin "1") (pinfunction "1_1") (pintype "passive"))
      (node (ref "U2") (pin "3") (pinfunction "VIN_3") (pintype "passive"))
      (node (ref "U8") (pin "3") (pinfunction "VCC_3") (pintype "passive"))
    )
    (net (code "62") (name "24V") (class "Default")
      (node (ref "C29") (pin "2") (pinfunction "2_2") (pintype "passive"))
      (node (ref "C3") (pin "1") (pinfunction "1_1") (pintype "passive"))
      (node (ref "C30") (pin "2") (pinfunction "2_2") (pintype "passive"))
      (node (ref "D2") (pin "2") (pinfunction "K_2") (pintype "passive"))
      (node (ref "G2") (pin "1") (pinfunction "A_1") (pintype "passive"))
      (node (ref "G3") (pin "1") (pinfunction "A_1") (pintype "passive"))
      (node (ref "G4") (pin "1") (pinfunction "A_1") (pintype "passive"))
      (node (ref "G5") (pin "1") (pinfunction "A_1") (pintype "passive"))
      (node (ref "I1") (pin "2") (pinfunction "2_2") (pintype "passive"))
      (node (ref "I4") (pin "1") (pinfunction "1_1") (pintype "passive"))
      (node (ref "K1") (pin "1") (pinfunction "1_1") (pintype "passive"))
      (node (ref "K2") (pin "1") (pinfunction "1_1") (pintype "passive"))
      (node (ref "P8") (pin "1") (pinfunction "1_1") (pintype "passive"))
      (node (ref "R13") (pin "2") (pinfunction "2_2") (pintype "passive"))
      (node (ref "R4") (pin "1") (pinfunction "1_1") (pintype "passive"))
      (node (ref "U1") (pin "5") (pinfunction "VIN_5") (pintype "passive"))
      (node (ref "U6") (pin "5") (pinfunction "COM_5") (pintype "passive"))
    )
    (net (code "63") (name "A3.3V") (class "Default")
      (node (ref "C28") (pin "2") (pinfunction "2_2") (pintype "passive"))
      (node (ref "C34") (pin "2") (pinfunction "2_2") (pintype "passive"))
      (node (ref "U10") (pin "2") (pinfunction "VOUT_2") (pintype "passive"))
      (node (ref "U5") (pin "13") (pinfunction "VDDA_13") (pintype "power_in"))
    )
    (net (code "64") (name "A24V") (class "Default")
      (node (ref "C31") (pin "2") (pinfunction "2_2") (pintype "passive"))
      (node (ref "C32") (pin "1") (pinfunction "1_1") (pintype "passive"))
      (node (ref "I4") (pin "2") (pinfunction "2_2") (pintype "passive"))
      (node (ref "U9") (pin "4") (pinfunction "V+_4") (pintype "power_in"))
    )
    (net (code "65") (name "AGND") (class "Default")
      (node (ref "C23") (pin "1") (pinfunction "1_1") (pintype "passive"))
      (node (ref "C24") (pin "1") (pinfunction "1_1") (pintype "passive"))
      (node (ref "C25") (pin "1") (pinfunction "1_1") (pintype "passive"))
      (node (ref "C26") (pin "1") (pinfunction "1_1") (pintype "passive"))
      (node (ref "C28") (pin "1") (pinfunction "1_1") (pintype "passive"))
      (node (ref "C31") (pin "1") (pinfunction "1_1") (pintype "passive"))
      (node (ref "C32") (pin "2") (pinfunction "2_2") (pintype "passive"))
      (node (ref "C33") (pin "1") (pinfunction "1_1") (pintype "passive"))
      (node (ref "C34") (pin "1") (pinfunction "1_1") (pintype "passive"))
      (node (ref "C37") (pin "1") (pinfunction "1_1") (pintype "passive"))
      (node (ref "D15") (pin "1") (pinfunction "A_1") (pintype "passive"))
      (node (ref "D19") (pin "1") (pinfunction "A_1") (pintype "passive"))
      (node (ref "D21") (pin "1") (pinfunction "A_1") (pintype "passive"))
      (node (ref "D22") (pin "1") (pinfunction "A_1") (pintype "passive"))
      (node (ref "D23") (pin "1") (pinfunction "A_1") (pintype "passive"))
      (node (ref "D24") (pin "1") (pinfunction "A_1") (pintype "passive"))
      (node (ref "P6") (pin "2") (pinfunction "2_2") (pintype "passive"))
      (node (ref "P6") (pin "5") (pinfunction "5_5") (pintype "passive"))
      (node (ref "P6") (pin "8") (pinfunction "8_8") (pintype "passive"))
      (node (ref "Q1") (pin "2") (pinfunction "S_2") (pintype "passive"))
      (node (ref "Q2") (pin "2") (pinfunction "S_2") (pintype "passive"))
      (node (ref "Q3") (pin "2") (pinfunction "S_2") (pintype "passive"))
      (node (ref "Q4") (pin "2") (pinfunction "S_2") (pintype "passive"))
      (node (ref "R34") (pin "1") (pinfunction "1_1") (pintype "passive"))
      (node (ref "R39") (pin "1") (pinfunction "1_1") (pintype "passive"))
      (node (ref "R43") (pin "1") (pinfunction "1_1") (pintype "passive"))
      (node (ref "R47") (pin "1") (pinfunction "1_1") (pintype "passive"))
      (node (ref "R49") (pin "2") (pinfunction "2_2") (pintype "passive"))
      (node (ref "R51") (pin "2") (pinfunction "2_2") (pintype "passive"))
      (node (ref "R52") (pin "2") (pinfunction "2_2") (pintype "passive"))
      (node (ref "U10") (pin "1") (pinfunction "VSS_1") (pintype "passive"))
      (node (ref "U5") (pin "12") (pinfunction "VSSA_12") (pintype "power_in"))
      (node (ref "U9") (pin "11") (pinfunction "V-_11") (pintype "power_in"))
    )
    (net (code "66") (name "GND") (class "Default")
      (node (ref "C10") (pin "1") (pinfunction "1_1") (pintype "passive"))
      (node (ref "C11") (pin "1") (pinfunction "1_1") (pintype "passive"))
      (node (ref "C16") (pin "1") (pinfunction "1_1") (pintype "passive"))
      (node (ref "C17") (pin "1") (pinfunction "1_1") (pintype "passive"))
      (node (ref "C18") (pin "1") (pinfunction "1_1") (pintype "passive"))
      (node (ref "C19") (pin "1") (pinfunction "1_1") (pintype "passive"))
      (node (ref "C2") (pin "2") (pinfunction "2_2") (pintype "passive"))
      (node (ref "C20") (pin "1") (pinfunction "1_1") (pintype "passive"))
      (node (ref "C21") (pin "1") (pinfunction "1_1") (pintype "passive"))
      (node (ref "C22") (pin "1") (pinfunction "1_1") (pintype "passive"))
      (node (ref "C27") (pin "2") (pinfunction "2_2") (pintype "passive"))
      (node (ref "C29") (pin "1") (pinfunction "1_1") (pintype "passive"))
      (node (ref "C3") (pin "2") (pinfunction "2_2") (pintype "passive"))
      (node (ref "C30") (pin "1") (pinfunction "1_1") (pintype "passive"))
      (node (ref "C35") (pin "1") (pinfunction "1_1") (pintype "passive"))
      (node (ref "C36") (pin "1") (pinfunction "1_1") (pintype "passive"))
      (node (ref "C38") (pin "2") (pinfunction "2_2") (pintype "passive"))
      (node (ref "C6") (pin "2") (pinfunction "2_2") (pintype "passive"))
      (node (ref "C8") (pin "1") (pinfunction "1_1") (pintype "passive"))
      (node (ref "C9") (pin "1") (pinfunction "1_1") (pintype "passive"))
      (node (ref "D10") (pin "1") (pinfunction "A_1") (pintype "passive"))
      (node (ref "D12") (pin "1") (pinfunction "A_1") (pintype "passive"))
      (node (ref "D14") (pin "1") (pinfunction "A_1") (pintype "passive"))
      (node (ref "D16") (pin "1") (pinfunction "A_1") (pintype "passive"))
      (node (ref "D17") (pin "1") (pinfunction "A_1") (pintype "passive"))
      (node (ref "D18") (pin "1") (pinfunction "A_1") (pintype "passive"))
      (node (ref "D2") (pin "1") (pinfunction "A_1") (pintype "passive"))
      (node (ref "D20") (pin "1") (pinfunction "A_1") (pintype "passive"))
      (node (ref "D3") (pin "1") (pinfunction "A_1") (pintype "passive"))
      (node (ref "D8") (pin "1") (pinfunction "A_1") (pintype "passive"))
      (node (ref "G2") (pin "3") (pinfunction "E_3") (pintype "passive"))
      (node (ref "G3") (pin "3") (pinfunction "E_3") (pintype "passive"))
      (node (ref "G4") (pin "3") (pinfunction "E_3") (pintype "passive"))
      (node (ref "G5") (pin "3") (pinfunction "E_3") (pintype "passive"))
      (node (ref "M1") (pin "1") (pinfunction "GND_1") (pintype "passive"))
      (node (ref "P10") (pin "2") (pinfunction "2_2") (pintype "passive"))
      (node (ref "P2") (pin "2") (pinfunction "2_2") (pintype "passive"))
      (node (ref "P2") (pin "5") (pinfunction "5_5") (pintype "passive"))
      (node (ref "P3") (pin "3") (pinfunction "3_3") (pintype "passive"))
      (node (ref "P8") (pin "2") (pinfunction "2_2") (pintype "passive"))
      (node (ref "R16") (pin "1") (pinfunction "1_1") (pintype "passive"))
      (node (ref "R23") (pin "2") (pinfunction "2_2") (pintype "passive"))
      (node (ref "R24") (pin "2") (pinfunction "2_2") (pintype "passive"))
      (node (ref "R35") (pin "1") (pinfunction "1_1") (pintype "passive"))
      (node (ref "R52") (pin "1") (pinfunction "1_1") (pintype "passive"))
      (node (ref "R9") (pin "2") (pinfunction "2_2") (pintype "passive"))
      (node (ref "T1") (pin "6") (pinfunction "6_6") (pintype "passive"))
      (node (ref "T1") (pin "7") (pinfunction "7_7") (pintype "passive"))
      (node (ref "U1") (pin "2") (pinfunction "GND_2") (pintype "passive"))
      (node (ref "U2") (pin "1") (pinfunction "VSS_1") (pintype "passive"))
      (node (ref "U4") (pin "3") (pinfunction "A_3") (pintype "passive"))
      (node (ref "U5") (pin "18") (pinfunction "VSS_4_18") (pintype "power_in"))
      (node (ref "U5") (pin "31") (pinfunction "VSS_1_31") (pintype "power_in"))
      (node (ref "U5") (pin "47") (pinfunction "VSS_2_47") (pintype "power_in"))
      (node (ref "U5") (pin "63") (pinfunction "VSS_3_63") (pintype "power_in"))
      (node (ref "U6") (pin "4") (pinfunction "E_4") (pintype "passive"))
      (node (ref "U7") (pin "5") (pinfunction "GND_5") (pintype "passive"))
      (node (ref "U8") (pin "2") (pinfunction "GND_2") (pintype "passive"))
      (node (ref "U8") (pin "8") (pinfunction "S_8") (pintype "passive"))
    )
    (net (code "67") (name "Net-(C4-Pad1)") (class "Default")
      (node (ref "C4") (pin "1") (pinfunction "1_1") (pintype "passive"))
      (node (ref "L1") (pin "4") (pinfunction "4_4") (pintype "passive"))
      (node (ref "R1") (pin "2") (pinfunction "2_2") (pintype "passive"))
      (node (ref "R5") (pin "2") (pinfunction "2_2") (pintype "passive"))
    )
    (net (code "68") (name "Net-(C5-Pad1)") (class "Default")
      (node (ref "C5") (pin "1") (pinfunction "1_1") (pintype "passive"))
      (node (ref "D5") (pin "2") (pinfunction "C_2") (pintype "passive"))
      (node (ref "L1") (pin "3") (pinfunction "3_3") (pintype "passive"))
    )
    (net (code "69") (name "Net-(C5-Pad2)") (class "Default")
      (node (ref "C5") (pin "2") (pinfunction "2_2") (pintype "passive"))
      (node (ref "D5") (pin "1") (pinfunction "C_1") (pintype "passive"))
      (node (ref "L1") (pin "2") (pinfunction "2_2") (pintype "passive"))
    )
    (net (code "70") (name "Net-(C7-Pad1)") (class "Default")
      (node (ref "C7") (pin "1") (pinfunction "1_1") (pintype "passive"))
      (node (ref "R2") (pin "1") (pinfunction "1_1") (pintype "passive"))
    )
    (net (code "71") (name "Net-(D1-A)") (class "Default")
      (node (ref "D1") (pin "1") (pinfunction "A_1") (pintype "passive"))
      (node (ref "T1") (pin "5") (pinfunction "5_5") (pintype "passive"))
      (node (ref "T1") (pin "8") (pinfunction "8_8") (pintype "passive"))
    )
    (net (code "72") (name "Net-(D1-K)") (class "Default")
      (node (ref "C2") (pin "1") (pinfunction "1_1") (pintype "passive"))
      (node (ref "D1") (pin "2") (pinfunction "K_2") (pintype "passive"))
      (node (ref "I1") (pin "1") (pinfunction "1_1") (pintype "passive"))
      (node (ref "R12") (pin "2") (pinfunction "2_2") (pintype "passive"))
    )
    (net (code "73") (name "Net-(D4-A)") (class "Default")
      (node (ref "D4") (pin "1") (pinfunction "A_1") (pintype "passive"))
      (node (ref "T1") (pin "2") (pinfunction "2_2") (pintype "passive"))
      (node (ref "U3") (pin "5") (pinfunction "Drain_5") (pintype "passive"))
      (node (ref "U3") (pin "6") (pinfunction "Drain_6") (pintype "passive"))
    )
    (net (code "74") (name "Net-(D4-K)") (class "Default")
      (node (ref "D4") (pin "2") (pinfunction "K_2") (pintype "passive"))
      (node (ref "R2") (pin "2") (pinfunction "2_2") (pintype "passive"))
      (node (ref "R3") (pin "1") (pinfunction "1_1") (pintype "passive"))
    )
    (net (code "75") (name "Net-(D5-K)") (class "Default")
      (node (ref "C12") (pin "1") (pinfunction "1_1") (pintype "passive"))
      (node (ref "C7") (pin "2") (pinfunction "2_2") (pintype "passive"))
      (node (ref "D5") (pin "3") (pinfunction "K_3") (pintype "passive"))
      (node (ref "R3") (pin "2") (pinfunction "2_2") (pintype "passive"))
      (node (ref "R6") (pin "1") (pinfunction "1_1") (pintype "passive"))
      (node (ref "T1") (pin "1") (pinfunction "1_1") (pintype "passive"))
    )
    (net (code "76") (name "Net-(D6-A)") (class "Default")
      (node (ref "D6") (pin "1") (pinfunction "A_1") (pintype "passive"))
      (node (ref "T1") (pin "4") (pinfunction "4_4") (pintype "passive"))
    )
    (net (code "77") (name "Net-(D6-K)") (class "Default")
      (node (ref "C13") (pin "1") (pinfunction "1_1") (pintype "passive"))
      (node (ref "D6") (pin "2") (pinfunction "K_2") (pintype "passive"))
      (node (ref "R10") (pin "2") (pinfunction "2_2") (pintype "passive"))
      (node (ref "R11") (pin "2") (pinfunction "2_2") (pintype "passive"))
      (node (ref "R8") (pin "2") (pinfunction "2_2") (pintype "passive"))
    )
    (net (code "78") (name "Net-(D25-K)") (class "Default")
      (node (ref "D25") (pin "2") (pinfunction "K_2") (pintype "passive"))
      (node (ref "R27") (pin "1") (pinfunction "1_1") (pintype "passive"))
    )
    (net (code "79") (name "Net-(F1-Pad2)") (class "Default")
      (node (ref "F1") (pin "2") (pinfunction "2_2") (pintype "passive"))
      (node (ref "R1") (pin "1") (pinfunction "1_1") (pintype "passive"))
    )
    (net (code "80") (name "Net-(G1-A)") (class "Default")
      (node (ref "G1") (pin "1") (pinfunction "A_1") (pintype "passive"))
      (node (ref "R12") (pin "1") (pinfunction "1_1") (pintype "passive"))
    )
    (net (code "81") (name "Net-(G1-C)") (class "Default")
      (node (ref "C15") (pin "2") (pinfunction "2_2") (pintype "passive"))
      (node (ref "G1") (pin "4") (pinfunction "C_4") (pintype "passive"))
      (node (ref "U3") (pin "1") (pinfunction "FB_1") (pintype "passive"))
    )
    (net (code "82") (name "Net-(G1-K)") (class "Default")
      (node (ref "C14") (pin "1") (pinfunction "1_1") (pintype "passive"))
      (node (ref "G1") (pin "2") (pinfunction "K_2") (pintype "passive"))
      (node (ref "U4") (pin "2") (pinfunction "K_2") (pintype "passive"))
    )
    (net (code "83") (name "Net-(G2-K)") (class "Default")
      (node (ref "C16") (pin "2") (pinfunction "2_2") (pintype "passive"))
      (node (ref "G2") (pin "2") (pinfunction "K_2") (pintype "passive"))
      (node (ref "R18") (pin "2") (pinfunction "2_2") (pintype "passive"))
    )
    (net (code "84") (name "Net-(G3-K)") (class "Default")
      (node (ref "C17") (pin "2") (pinfunction "2_2") (pintype "passive"))
      (node (ref "G3") (pin "2") (pinfunction "K_2") (pintype "passive"))
      (node (ref "R20") (pin "2") (pinfunction "2_2") (pintype "passive"))
    )
    (net (code "85") (name "Net-(G4-K)") (class "Default")
      (node (ref "C19") (pin "2") (pinfunction "2_2") (pintype "passive"))
      (node (ref "G4") (pin "2") (pinfunction "K_2") (pintype "passive"))
      (node (ref "R22") (pin "2") (pinfunction "2_2") (pintype "passive"))
    )
    (net (code "86") (name "Net-(G5-K)") (class "Default")
      (node (ref "C22") (pin "2") (pinfunction "2_2") (pintype "passive"))
      (node (ref "G5") (pin "2") (pinfunction "K_2") (pintype "passive"))
      (node (ref "R26") (pin "2") (pinfunction "2_2") (pintype "passive"))
    )
    (net (code "87") (name "Net-(P4-Pad1)") (class "Default")
      (node (ref "P4") (pin "1") (pinfunction "1_1") (pintype "passive"))
      (node (ref "R32") (pin "2") (pinfunction "2_2") (pintype "passive"))
    )
    (net (code "88") (name "Net-(P9-Pad2)") (class "Default")
      (node (ref "P9") (pin "2") (pinfunction "2_2") (pintype "passive"))
      (node (ref "R53") (pin "1") (pinfunction "1_1") (pintype "passive"))
    )
    (net (code "89") (name "Net-(Q1-D)") (class "Default")
      (node (ref "Q1") (pin "3") (pinfunction "D_3") (pintype "passive"))
      (node (ref "R29") (pin "1") (pinfunction "1_1") (pintype "passive"))
      (node (ref "R30") (pin "1") (pinfunction "1_1") (pintype "passive"))
    )
    (net (code "90") (name "Net-(Q2-D)") (class "Default")
      (node (ref "Q2") (pin "3") (pinfunction "D_3") (pintype "passive"))
      (node (ref "R36") (pin "1") (pinfunction "1_1") (pintype "passive"))
      (node (ref "R37") (pin "1") (pinfunction "1_1") (pintype "passive"))
    )
    (net (code "91") (name "Net-(Q3-D)") (class "Default")
      (node (ref "Q3") (pin "3") (pinfunction "D_3") (pintype "passive"))
      (node (ref "R40") (pin "1") (pinfunction "1_1") (pintype "passive"))
      (node (ref "R41") (pin "1") (pinfunction "1_1") (pintype "passive"))
    )
    (net (code "92") (name "Net-(Q4-D)") (class "Default")
      (node (ref "Q4") (pin "3") (pinfunction "D_3") (pintype "passive"))
      (node (ref "R44") (pin "1") (pinfunction "1_1") (pintype "passive"))
      (node (ref "R45") (pin "1") (pinfunction "1_1") (pintype "passive"))
    )
    (net (code "93") (name "Net-(R6-Pad2)") (class "Default")
      (node (ref "R6") (pin "2") (pinfunction "2_2") (pintype "passive"))
      (node (ref "R8") (pin "1") (pinfunction "1_1") (pintype "passive"))
    )
    (net (code "94") (name "Net-(U1-BST)") (class "Default")
      (node (ref "C1") (pin "2") (pinfunction "2_2") (pintype "passive"))
      (node (ref "U1") (pin "1") (pinfunction "BST_1") (pintype "passive"))
    )
    (net (code "95") (name "Net-(U1-EN)") (class "Default")
      (node (ref "R4") (pin "2") (pinfunction "2_2") (pintype "passive"))
      (node (ref "U1") (pin "4") (pinfunction "EN_4") (pintype "passive"))
    )
    (net (code "96") (name "Net-(U1-FB)") (class "Default")
      (node (ref "R7") (pin "2") (pinfunction "2_2") (pintype "passive"))
      (node (ref "R9") (pin "1") (pinfunction "1_1") (pintype "passive"))
      (node (ref "U1") (pin "3") (pinfunction "FB_3") (pintype "passive"))
    )
    (net (code "97") (name "Net-(U1-SW)") (class "Default")
      (node (ref "C1") (pin "1") (pinfunction "1_1") (pintype "passive"))
      (node (ref "I2") (pin "1") (pinfunction "1_1") (pintype "passive"))
      (node (ref "U1") (pin "6") (pinfunction "SW_6") (pintype "passive"))
    )
    (net (code "98") (name "Net-(U3-Sense)") (class "Default")
      (node (ref "R14") (pin "2") (pinfunction "2_2") (pintype "passive"))
      (node (ref "R15") (pin "2") (pinfunction "2_2") (pintype "passive"))
      (node (ref "U3") (pin "4") (pinfunction "Sense_4") (pintype "passive"))
    )
    (net (code "99") (name "Net-(U3-VDD)") (class "Default")
      (node (ref "R11") (pin "1") (pinfunction "1_1") (pintype "passive"))
      (node (ref "U3") (pin "3") (pinfunction "VDD_3") (pintype "passive"))
    )
    (net (code "100") (name "Net-(U3-VDD_G)") (class "Default")
      (node (ref "R10") (pin "1") (pinfunction "1_1") (pintype "passive"))
      (node (ref "U3") (pin "2") (pinfunction "VDD_G_2") (pintype "passive"))
    )
    (net (code "101") (name "Net-(U4-REF)") (class "Default")
      (node (ref "C14") (pin "2") (pinfunction "2_2") (pintype "passive"))
      (node (ref "R13") (pin "1") (pinfunction "1_1") (pintype "passive"))
      (node (ref "R16") (pin "2") (pinfunction "2_2") (pintype "passive"))
      (node (ref "U4") (pin "1") (pinfunction "REF_1") (pintype "passive"))
    )
    (net (code "102") (name "Net-(U5-BOOT0)") (class "Default")
      (node (ref "R23") (pin "1") (pinfunction "1_1") (pintype "passive"))
      (node (ref "U5") (pin "60") (pinfunction "BOOT0_60") (pintype "input"))
    )
    (net (code "103") (name "Net-(U5-PB2)") (class "Default")
      (node (ref "R24") (pin "1") (pinfunction "1_1") (pintype "passive"))
      (node (ref "U5") (pin "28") (pinfunction "PB2_28") (pintype "bidirectional"))
    )
    (net (code "104") (name "Net-(U5-PD0-OSC_IN)") (class "Default")
      (node (ref "C20") (pin "2") (pinfunction "2_2") (pintype "passive"))
      (node (ref "U5") (pin "5") (pinfunction "PD0-OSC_IN_5") (pintype "bidirectional"))
      (node (ref "Y1") (pin "2") (pinfunction "OSC2_2") (pintype "passive"))
    )
    (net (code "105") (name "Net-(U5-PD1)") (class "Default")
      (node (ref "C21") (pin "2") (pinfunction "2_2") (pintype "passive"))
      (node (ref "U5") (pin "6") (pinfunction "PD1_6") (pintype "bidirectional"))
      (node (ref "Y1") (pin "1") (pinfunction "OSC1_1") (pintype "passive"))
    )
    (net (code "106") (name "Net-(U6-2C)") (class "Default")
      (node (ref "K1") (pin "2") (pinfunction "2_2") (pintype "passive"))
      (node (ref "U6") (pin "7") (pinfunction "2C_7") (pintype "passive"))
    )
    (net (code "107") (name "Net-(U6-3C)") (class "Default")
      (node (ref "K2") (pin "2") (pinfunction "2_2") (pintype "passive"))
      (node (ref "U6") (pin "6") (pinfunction "3C_6") (pintype "passive"))
    )
    (net (code "108") (name "Net-(U7-A)") (class "Default")
      (node (ref "R28") (pin "2") (pinfunction "2_2") (pintype "passive"))
      (node (ref "U7") (pin "6") (pinfunction "A_6") (pintype "passive"))
    )
    (net (code "109") (name "Net-(U7-B)") (class "Default")
      (node (ref "R33") (pin "2") (pinfunction "2_2") (pintype "passive"))
      (node (ref "U7") (pin "7") (pinfunction "B_7") (pintype "passive"))
    )
    (net (code "110") (name "Net-(U9A-IN-)") (class "Default")
      (node (ref "R50") (pin "1") (pinfunction "1_1") (pintype "passive"))
      (node (ref "R51") (pin "1") (pinfunction "1_1") (pintype "passive"))
      (node (ref "U9") (pin "2") (pinfunction "IN-_2") (pintype "input"))
    )
    (net (code "111") (name "Net-(U9A-OUT)") (class "Default")
      (node (ref "R50") (pin "2") (pinfunction "2_2") (pintype "passive"))
      (node (ref "U9") (pin "1") (pinfunction "OUT_1") (pintype "output"))
      (node (ref "U9") (pin "5") (pinfunction "IN+_5") (pintype "input"))
    )
    (net (code "112") (name "Net-(U9C-IN+)") (class "Default")
      (node (ref "R48") (pin "2") (pinfunction "2_2") (pintype "passive"))
      (node (ref "U9") (pin "10") (pinfunction "IN+_10") (pintype "input"))
      (node (ref "U9") (pin "14") (pinfunction "OUT_14") (pintype "output"))
    )
    (net (code "113") (name "Net-(U9D-IN-)") (class "Default")
      (node (ref "R48") (pin "1") (pinfunction "1_1") (pintype "passive"))
      (node (ref "R49") (pin "1") (pinfunction "1_1") (pintype "passive"))
      (node (ref "U9") (pin "13") (pinfunction "IN-_13") (pintype "input"))
    )
    (net (code "114") (name "Net-(U10-VIN)") (class "Default")
      (node (ref "C33") (pin "2") (pinfunction "2_2") (pintype "passive"))
      (node (ref "C37") (pin "2") (pinfunction "2_2") (pintype "passive"))
      (node (ref "I3") (pin "1") (pinfunction "1_1") (pintype "passive"))
      (node (ref "U10") (pin "3") (pinfunction "VIN_3") (pintype "passive"))
    )
    (net (code "115") (name "unconnected-(M1-GPIO0-Pad11)") (class "Default")
      (node (ref "M1") (pin "11") (pinfunction "GPIO0_11") (pintype "passive+no_connect"))
    )
    (net (code "116") (name "unconnected-(M1-GPIO1-Pad10)") (class "Default")
      (node (ref "M1") (pin "10") (pinfunction "GPIO1_10") (pintype "passive+no_connect"))
    )
    (net (code "117") (name "unconnected-(M1-GPIO2-Pad4)") (class "Default")
      (node (ref "M1") (pin "4") (pinfunction "GPIO2_4") (pintype "passive+no_connect"))
    )
    (net (code "118") (name "unconnected-(M1-GPIO3-Pad3)") (class "Default")
      (node (ref "M1") (pin "3") (pinfunction "GPIO3_3") (pintype "passive+no_connect"))
    )
    (net (code "119") (name "unconnected-(U5-PA15-Pad50)") (class "Default")
      (node (ref "U5") (pin "50") (pinfunction "PA15_50") (pintype "bidirectional+no_connect"))
    )
    (net (code "120") (name "unconnected-(U5-PB8-Pad61)") (class "Default")
      (node (ref "U5") (pin "61") (pinfunction "PB8_61") (pintype "bidirectional+no_connect"))
    )
    (net (code "121") (name "unconnected-(U5-PB9-Pad62)") (class "Default")
      (node (ref "U5") (pin "62") (pinfunction "PB9_62") (pintype "bidirectional+no_connect"))
    )
    (net (code "122") (name "unconnected-(U5-PC0-Pad8)") (class "Default")
      (node (ref "U5") (pin "8") (pinfunction "PC0_8") (pintype "bidirectional+no_connect"))
    )
    (net (code "123") (name "unconnected-(U5-PC1-Pad9)") (class "Default")
      (node (ref "U5") (pin "9") (pinfunction "PC1_9") (pintype "bidirectional+no_connect"))
    )
    (net (code "124") (name "unconnected-(U5-PC2-Pad10)") (class "Default")
      (node (ref "U5") (pin "10") (pinfunction "PC2_10") (pintype "bidirectional+no_connect"))
    )
    (net (code "125") (name "unconnected-(U5-PC3-Pad11)") (class "Default")
      (node (ref "U5") (pin "11") (pinfunction "PC3_11") (pintype "bidirectional+no_connect"))
    )
    (net (code "126") (name "unconnected-(U5-PC8-Pad39)") (class "Default")
      (node (ref "U5") (pin "39") (pinfunction "PC8_39") (pintype "bidirectional+no_connect"))
    )
    (net (code "127") (name "unconnected-(U5-PC9-Pad40)") (class "Default")
      (node (ref "U5") (pin "40") (pinfunction "PC9_40") (pintype "bidirectional+no_connect"))
    )
    (net (code "128") (name "unconnected-(U5-PC10-Pad51)") (class "Default")
      (node (ref "U5") (pin "51") (pinfunction "PC10_51") (pintype "bidirectional+no_connect"))
    )
    (net (code "129") (name "unconnected-(U5-PC13-TAMPER-RTC-Pad2)") (class "Default")
      (node (ref "U5") (pin "2") (pinfunction "PC13-TAMPER-RTC_2") (pintype "bidirectional+no_connect"))
    )
    (net (code "130") (name "unconnected-(U6-1B-Pad1)") (class "Default")
      (node (ref "U6") (pin "1") (pinfunction "1B_1") (pintype "passive+no_connect"))
    )
    (net (code "131") (name "unconnected-(U6-1C-Pad8)") (class "Default")
      (node (ref "U6") (pin "8") (pinfunction "1C_8") (pintype "passive+no_connect"))
    )
  )
)
